# manpad.net
KiCad netlist of a schematic drawn in EAGLE
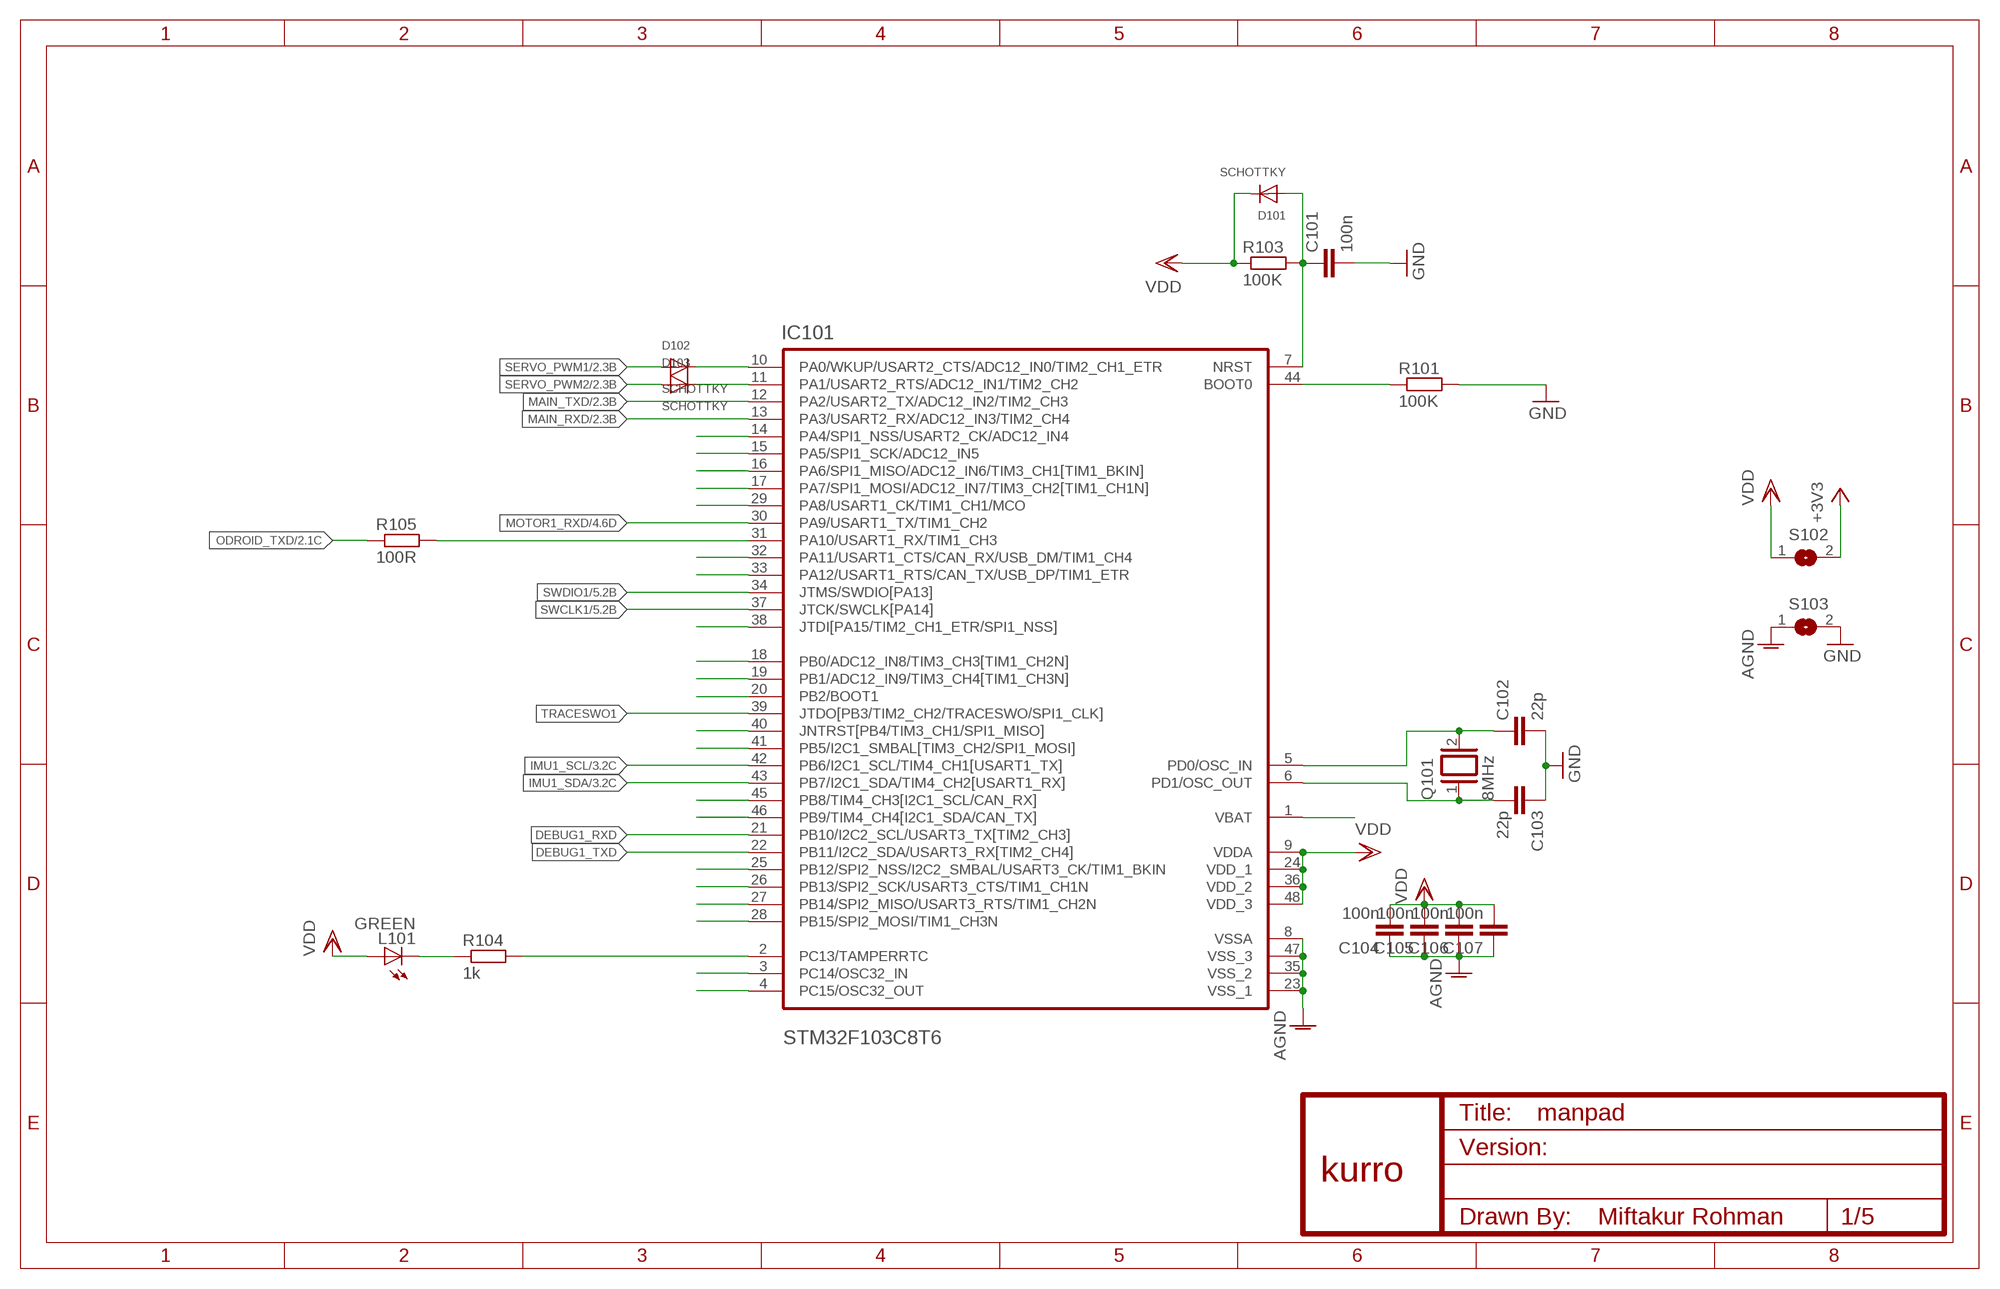
[diagram p0: schematic, sheet 1]
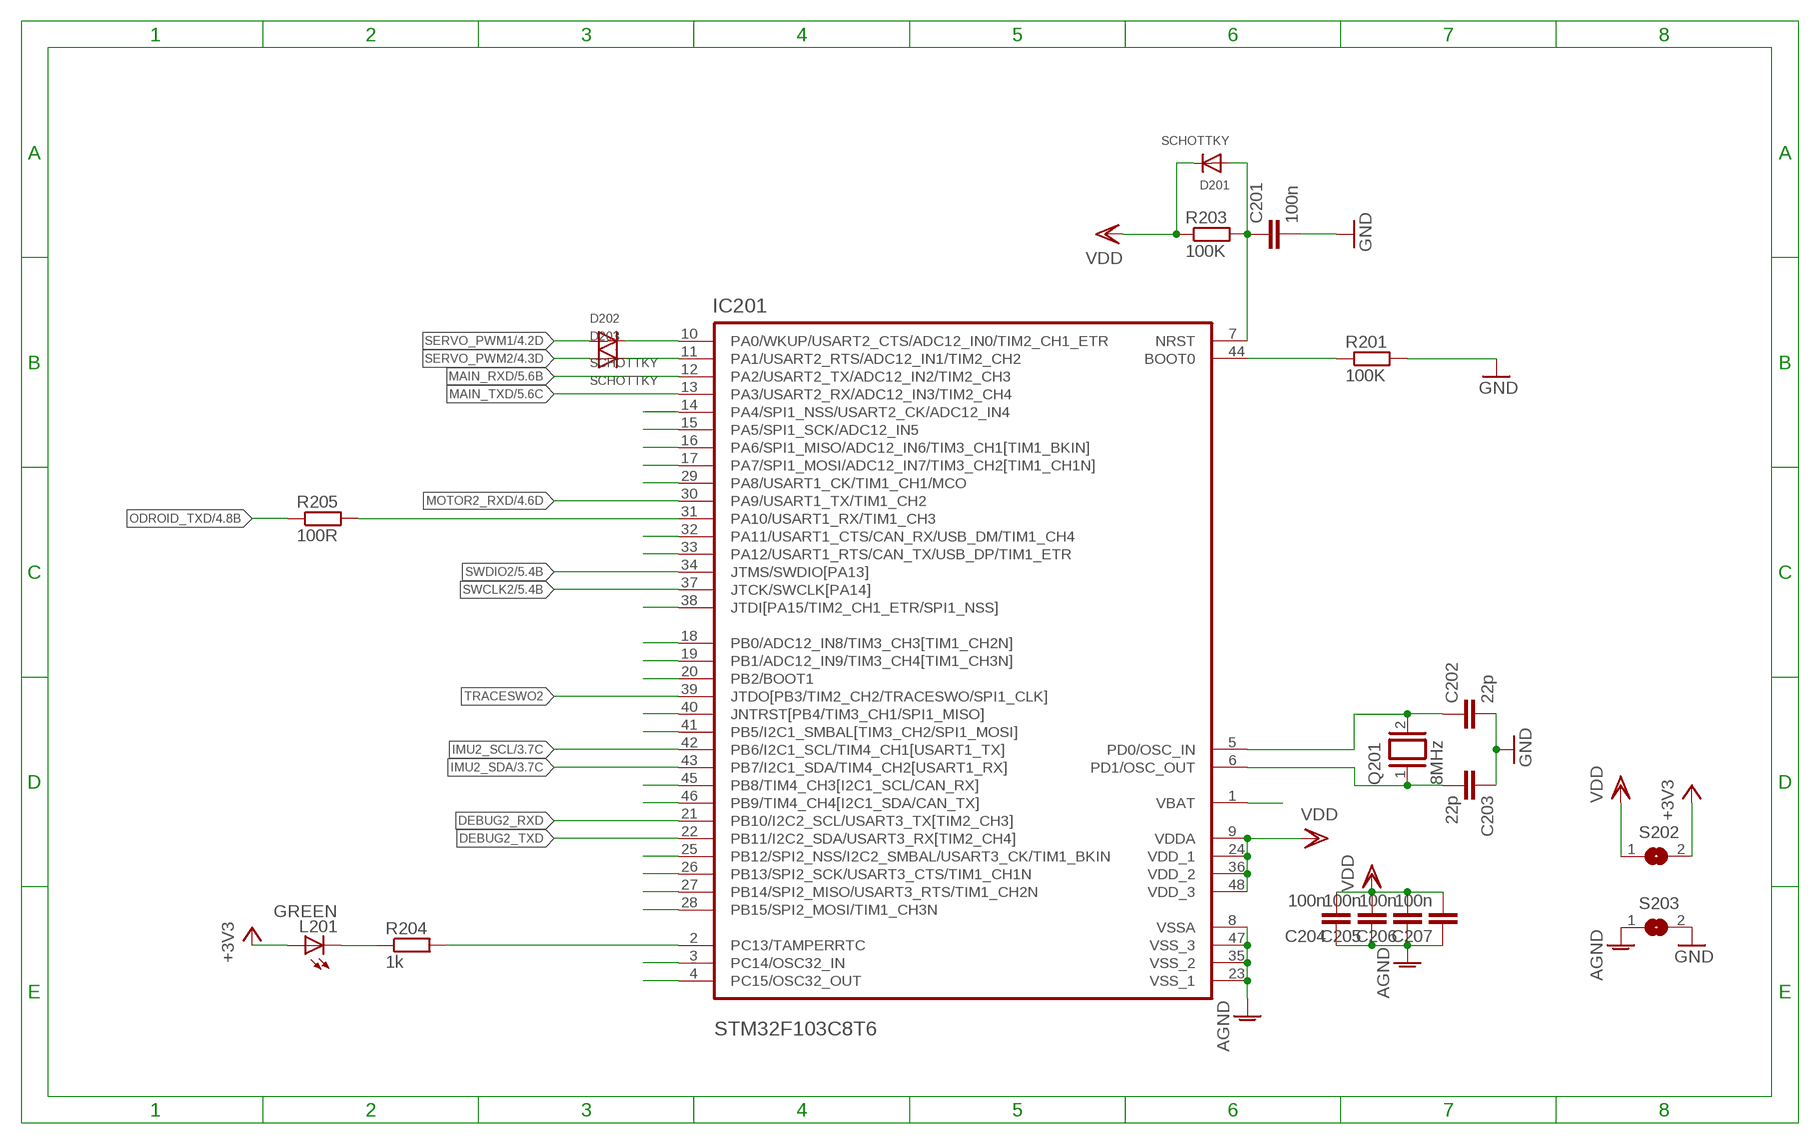
[diagram p1: schematic, sheet 2]
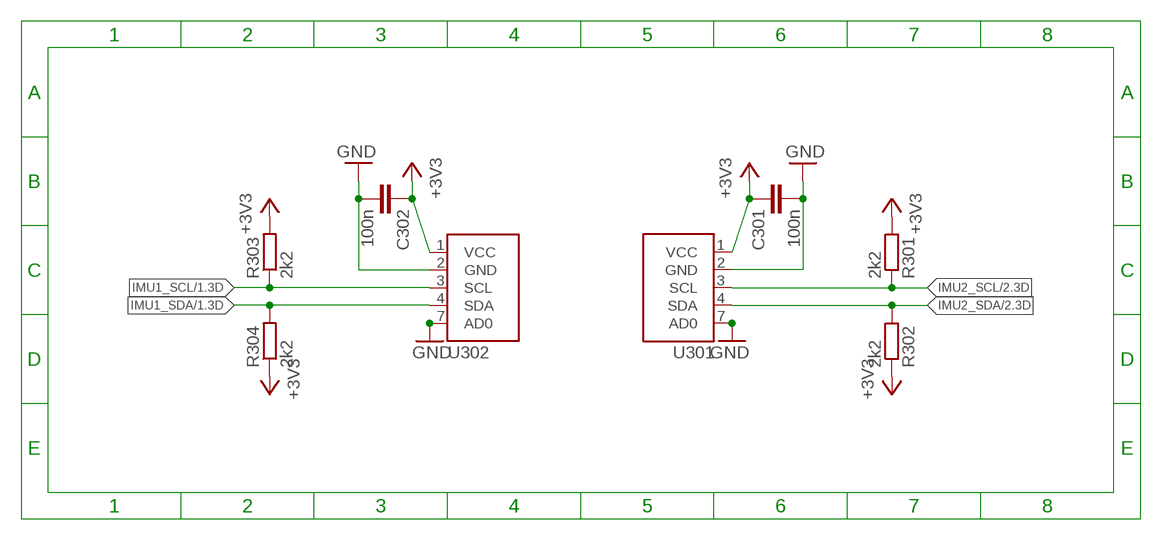
[diagram p2: schematic, sheet 3]
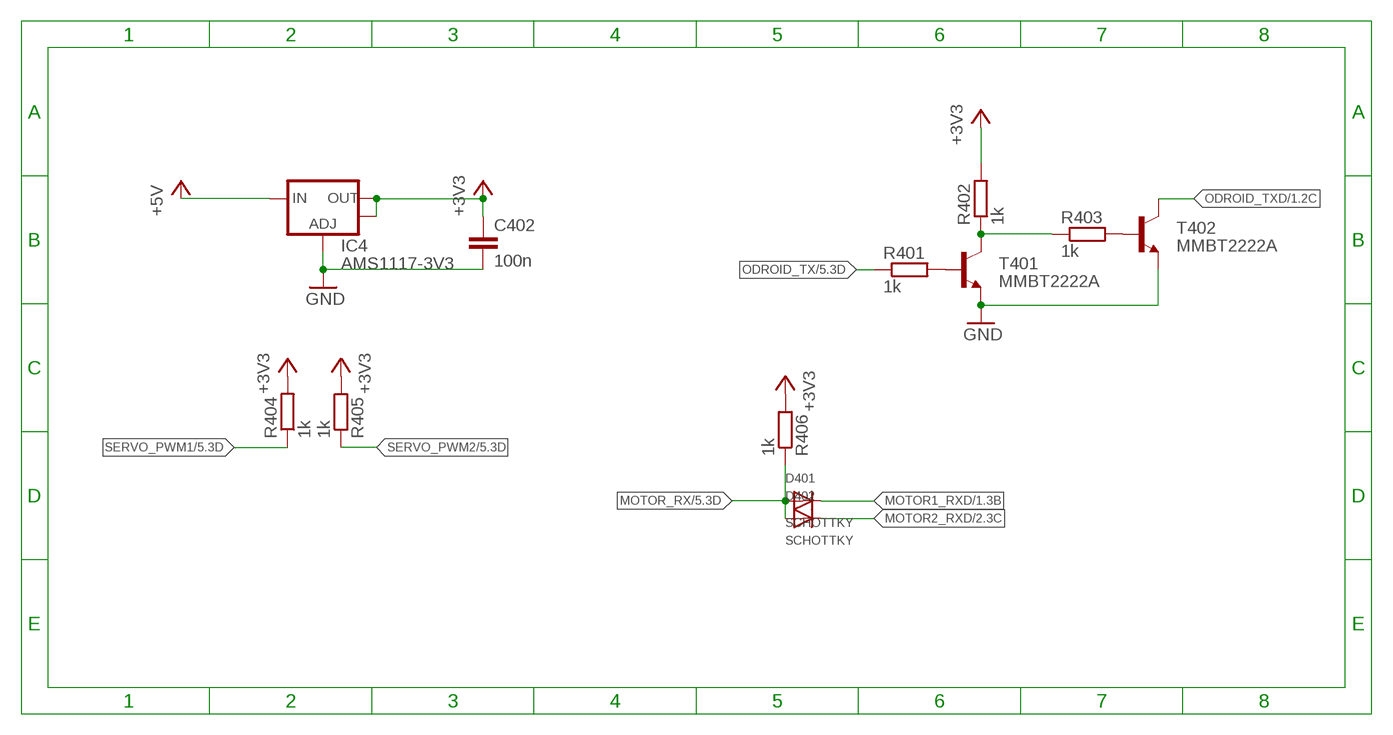
[diagram p3: schematic, sheet 4]
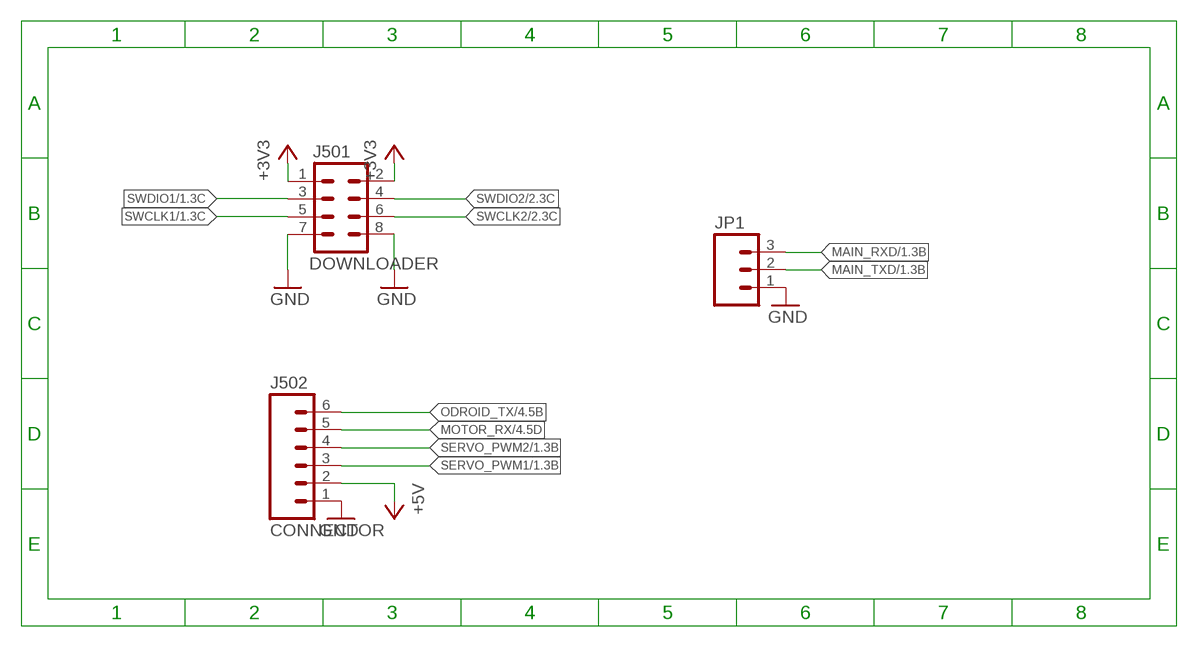
[diagram p4: schematic, sheet 5]

(export (version "E")
  (design (tool "Eeschema 10.0.6"))
  (components
    (comp (ref "C201")
      (value "100n")
      (footprint "eagle-import:C0603")
      (libsource (lib "eagle-import") (part "C-EUC0603"))
    )
    (comp (ref "C202")
      (value "22p")
      (footprint "eagle-import:C0603")
      (libsource (lib "eagle-import") (part "C-EUC0603"))
    )
    (comp (ref "C203")
      (value "22p")
      (footprint "eagle-import:C0603")
      (libsource (lib "eagle-import") (part "C-EUC0603"))
    )
    (comp (ref "C204")
      (value "100n")
      (footprint "eagle-import:C0603")
      (libsource (lib "eagle-import") (part "C-EUC0603"))
    )
    (comp (ref "C205")
      (value "100n")
      (footprint "eagle-import:C0603")
      (libsource (lib "eagle-import") (part "C-EUC0603"))
    )
    (comp (ref "C206")
      (value "100n")
      (footprint "eagle-import:C0603")
      (libsource (lib "eagle-import") (part "C-EUC0603"))
    )
    (comp (ref "C207")
      (value "100n")
      (footprint "eagle-import:C0603")
      (libsource (lib "eagle-import") (part "C-EUC0603"))
    )
    (comp (ref "D201")
      (value "SCHOTTKY")
      (footprint "eagle-import:SOD-323F")
      (libsource (lib "eagle-import") (part "DIODESOD-323F"))
    )
    (comp (ref "D202")
      (value "SCHOTTKY")
      (footprint "eagle-import:SOD-323F")
      (libsource (lib "eagle-import") (part "DIODESOD-323F"))
    )
    (comp (ref "D203")
      (value "SCHOTTKY")
      (footprint "eagle-import:SOD-323F")
      (libsource (lib "eagle-import") (part "DIODESOD-323F"))
    )
    (comp (ref "IC201")
      (value "STM32F103C8T6")
      (footprint "eagle-import:QFP50P900X900X160-48N")
      (fields (field (name "MPN") "STM32F103CBT6"))
      (libsource (lib "eagle-import") (part "STM32F103C8T6"))
    )
    (comp (ref "L201")
      (value "GREEN")
      (footprint "eagle-import:CHIP-LED0805")
      (libsource (lib "eagle-import") (part "LEDCHIP-LED0805"))
    )
    (comp (ref "Q201")
      (value "8MHz")
      (footprint "eagle-import:QS")
      (libsource (lib "eagle-import") (part "XTAL/S"))
    )
    (comp (ref "R201")
      (value "100K")
      (footprint "eagle-import:R0603")
      (libsource (lib "eagle-import") (part "R-EU_R0603"))
    )
    (comp (ref "R203")
      (value "100K")
      (footprint "eagle-import:R0603")
      (libsource (lib "eagle-import") (part "R-EU_R0603"))
    )
    (comp (ref "R204")
      (value "1k")
      (footprint "eagle-import:R0603")
      (libsource (lib "eagle-import") (part "R-EU_R0603"))
    )
    (comp (ref "R205")
      (value "100R")
      (footprint "eagle-import:R0603")
      (libsource (lib "eagle-import") (part "R-EU_R0603"))
    )
    (comp (ref "S202")
      (value "SJS")
      (footprint "eagle-import:SJS")
      (libsource (lib "eagle-import") (part "SJS"))
    )
    (comp (ref "S203")
      (value "SJS")
      (footprint "eagle-import:SJS")
      (libsource (lib "eagle-import") (part "SJS"))
    )
    (comp (ref "J501")
      (value "DOWNLOADER")
      (footprint "eagle-import:2X4_SMD")
      (libsource (lib "eagle-import") (part "M04X2FEMALE_SMD"))
    )
    (comp (ref "J502")
      (value "CONNECTOR")
      (footprint "eagle-import:XH-6-RA")
      (libsource (lib "eagle-import") (part "M06-XH-RA"))
    )
    (comp (ref "JP1")
      (value "M03LOCK")
      (footprint "eagle-import:1X03_LOCK")
      (libsource (lib "eagle-import") (part "M03LOCK"))
    )
    (comp (ref "C101")
      (value "100n")
      (footprint "eagle-import:C0603")
      (libsource (lib "eagle-import") (part "C-EUC0603"))
    )
    (comp (ref "C102")
      (value "22p")
      (footprint "eagle-import:C0603")
      (libsource (lib "eagle-import") (part "C-EUC0603"))
    )
    (comp (ref "C103")
      (value "22p")
      (footprint "eagle-import:C0603")
      (libsource (lib "eagle-import") (part "C-EUC0603"))
    )
    (comp (ref "C104")
      (value "100n")
      (footprint "eagle-import:C0603")
      (libsource (lib "eagle-import") (part "C-EUC0603"))
    )
    (comp (ref "C105")
      (value "100n")
      (footprint "eagle-import:C0603")
      (libsource (lib "eagle-import") (part "C-EUC0603"))
    )
    (comp (ref "C106")
      (value "100n")
      (footprint "eagle-import:C0603")
      (libsource (lib "eagle-import") (part "C-EUC0603"))
    )
    (comp (ref "C107")
      (value "100n")
      (footprint "eagle-import:C0603")
      (libsource (lib "eagle-import") (part "C-EUC0603"))
    )
    (comp (ref "D101")
      (value "SCHOTTKY")
      (footprint "eagle-import:SOD-323F")
      (libsource (lib "eagle-import") (part "DIODESOD-323F"))
    )
    (comp (ref "D102")
      (value "SCHOTTKY")
      (footprint "eagle-import:SOD-323F")
      (libsource (lib "eagle-import") (part "DIODESOD-323F"))
    )
    (comp (ref "D103")
      (value "SCHOTTKY")
      (footprint "eagle-import:SOD-323F")
      (libsource (lib "eagle-import") (part "DIODESOD-323F"))
    )
    (comp (ref "IC101")
      (value "STM32F103C8T6")
      (footprint "eagle-import:QFP50P900X900X160-48N")
      (fields (field (name "MPN") "STM32F103CBT6"))
      (libsource (lib "eagle-import") (part "STM32F103C8T6"))
    )
    (comp (ref "L101")
      (value "GREEN")
      (footprint "eagle-import:CHIP-LED0805")
      (libsource (lib "eagle-import") (part "LEDCHIP-LED0805"))
    )
    (comp (ref "Q101")
      (value "8MHz")
      (footprint "eagle-import:QS")
      (libsource (lib "eagle-import") (part "XTAL/S"))
    )
    (comp (ref "R101")
      (value "100K")
      (footprint "eagle-import:R0603")
      (libsource (lib "eagle-import") (part "R-EU_R0603"))
    )
    (comp (ref "R103")
      (value "100K")
      (footprint "eagle-import:R0603")
      (libsource (lib "eagle-import") (part "R-EU_R0603"))
    )
    (comp (ref "R104")
      (value "1k")
      (footprint "eagle-import:R0603")
      (libsource (lib "eagle-import") (part "R-EU_R0603"))
    )
    (comp (ref "R105")
      (value "100R")
      (footprint "eagle-import:R0603")
      (libsource (lib "eagle-import") (part "R-EU_R0603"))
    )
    (comp (ref "S102")
      (value "SJS")
      (footprint "eagle-import:SJS")
      (libsource (lib "eagle-import") (part "SJS"))
    )
    (comp (ref "S103")
      (value "SJS")
      (footprint "eagle-import:SJS")
      (libsource (lib "eagle-import") (part "SJS"))
    )
    (comp (ref "U$1")
      (value "KURRO_FOOTPRINT")
      (footprint "eagle-import:KURRO-LOGO")
      (libsource (lib "eagle-import") (part "KURRO_FOOTPRINT"))
    )
    (comp (ref "C402")
      (value "100n")
      (footprint "eagle-import:C0603")
      (libsource (lib "eagle-import") (part "C-EUC0603"))
    )
    (comp (ref "D401")
      (value "SCHOTTKY")
      (footprint "eagle-import:SOD-323F")
      (libsource (lib "eagle-import") (part "DIODESOD-323F"))
    )
    (comp (ref "D402")
      (value "SCHOTTKY")
      (footprint "eagle-import:SOD-323F")
      (libsource (lib "eagle-import") (part "DIODESOD-323F"))
    )
    (comp (ref "IC4")
      (value "AMS1117-3V3")
      (footprint "eagle-import:SOT223")
      (libsource (lib "eagle-import") (part "V_REG_LM1117SOT223"))
    )
    (comp (ref "R401")
      (value "1k")
      (footprint "eagle-import:R0603")
      (libsource (lib "eagle-import") (part "R-EU_R0603"))
    )
    (comp (ref "R402")
      (value "1k")
      (footprint "eagle-import:R0603")
      (libsource (lib "eagle-import") (part "R-EU_R0603"))
    )
    (comp (ref "R403")
      (value "1k")
      (footprint "eagle-import:R0603")
      (libsource (lib "eagle-import") (part "R-EU_R0603"))
    )
    (comp (ref "R404")
      (value "1k")
      (footprint "eagle-import:R0603")
      (libsource (lib "eagle-import") (part "R-EU_R0603"))
    )
    (comp (ref "R405")
      (value "1k")
      (footprint "eagle-import:R0603")
      (libsource (lib "eagle-import") (part "R-EU_R0603"))
    )
    (comp (ref "R406")
      (value "1k")
      (footprint "eagle-import:R0603")
      (libsource (lib "eagle-import") (part "R-EU_R0603"))
    )
    (comp (ref "T401")
      (value "MMBT2222A")
      (footprint "eagle-import:SOT23")
      (libsource (lib "eagle-import") (part "TRANSISTOR_NPNSOT23"))
    )
    (comp (ref "T402")
      (value "MMBT2222A")
      (footprint "eagle-import:SOT23")
      (libsource (lib "eagle-import") (part "TRANSISTOR_NPNSOT23"))
    )
    (comp (ref "C301")
      (value "100n")
      (footprint "eagle-import:C0603")
      (libsource (lib "eagle-import") (part "C-EUC0603"))
    )
    (comp (ref "C302")
      (value "100n")
      (footprint "eagle-import:C0603")
      (libsource (lib "eagle-import") (part "C-EUC0603"))
    )
    (comp (ref "R301")
      (value "2k2")
      (footprint "eagle-import:R0603")
      (libsource (lib "eagle-import") (part "R-EU_R0603"))
    )
    (comp (ref "R302")
      (value "2k2")
      (footprint "eagle-import:R0603")
      (libsource (lib "eagle-import") (part "R-EU_R0603"))
    )
    (comp (ref "R303")
      (value "2k2")
      (footprint "eagle-import:R0603")
      (libsource (lib "eagle-import") (part "R-EU_R0603"))
    )
    (comp (ref "R304")
      (value "2k2")
      (footprint "eagle-import:R0603")
      (libsource (lib "eagle-import") (part "R-EU_R0603"))
    )
    (comp (ref "U301")
      (value "GY-521_MIN")
      (footprint "eagle-import:GY-521_MINNH")
      (libsource (lib "eagle-import") (part "GY-521_MIN"))
    )
    (comp (ref "U302")
      (value "GY-521_MIN")
      (footprint "eagle-import:GY-521_MINNH")
      (libsource (lib "eagle-import") (part "GY-521_MIN"))
    )
  )
  (nets
    (net (code "1") (name "+3V3") (class "Default")
      (node (ref "C301") (pin "1") (pinfunction "1_1") (pintype "passive"))
      (node (ref "C302") (pin "1") (pinfunction "1_1") (pintype "passive"))
      (node (ref "C402") (pin "1") (pinfunction "1_1") (pintype "passive"))
      (node (ref "IC4") (pin "2") (pinfunction "OUT_2") (pintype "power_in"))
      (node (ref "IC4") (pin "4") (pinfunction "OUT_4") (pintype "power_in"))
      (node (ref "J501") (pin "1") (pinfunction "1_1") (pintype "passive"))
      (node (ref "J501") (pin "2") (pinfunction "2_2") (pintype "passive"))
      (node (ref "L201") (pin "A") (pinfunction "A_A") (pintype "passive"))
      (node (ref "R301") (pin "2") (pinfunction "2_2") (pintype "passive"))
      (node (ref "R302") (pin "1") (pinfunction "1_1") (pintype "passive"))
      (node (ref "R303") (pin "2") (pinfunction "2_2") (pintype "passive"))
      (node (ref "R304") (pin "1") (pinfunction "1_1") (pintype "passive"))
      (node (ref "R402") (pin "2") (pinfunction "2_2") (pintype "passive"))
      (node (ref "R404") (pin "2") (pinfunction "2_2") (pintype "passive"))
      (node (ref "R405") (pin "2") (pinfunction "2_2") (pintype "passive"))
      (node (ref "R406") (pin "2") (pinfunction "2_2") (pintype "passive"))
      (node (ref "S102") (pin "2") (pinfunction "2_2") (pintype "passive"))
      (node (ref "S202") (pin "2") (pinfunction "2_2") (pintype "passive"))
      (node (ref "U301") (pin "1") (pinfunction "VCC_1") (pintype "bidirectional"))
      (node (ref "U302") (pin "1") (pinfunction "VCC_1") (pintype "bidirectional"))
    )
    (net (code "2") (name "+5V") (class "Default")
      (node (ref "IC4") (pin "3") (pinfunction "IN_3") (pintype "input"))
      (node (ref "J502") (pin "2") (pinfunction "2_2") (pintype "passive"))
    )
    (net (code "3") (name "AGND") (class "Default")
      (node (ref "C104") (pin "1") (pinfunction "1_1") (pintype "passive"))
      (node (ref "C105") (pin "1") (pinfunction "1_1") (pintype "passive"))
      (node (ref "C106") (pin "1") (pinfunction "1_1") (pintype "passive"))
      (node (ref "C107") (pin "1") (pinfunction "1_1") (pintype "passive"))
      (node (ref "C204") (pin "1") (pinfunction "1_1") (pintype "passive"))
      (node (ref "C205") (pin "1") (pinfunction "1_1") (pintype "passive"))
      (node (ref "C206") (pin "1") (pinfunction "1_1") (pintype "passive"))
      (node (ref "C207") (pin "1") (pinfunction "1_1") (pintype "passive"))
      (node (ref "IC101") (pin "23") (pinfunction "VSS_1_23") (pintype "bidirectional"))
      (node (ref "IC101") (pin "35") (pinfunction "VSS_2_35") (pintype "passive"))
      (node (ref "IC101") (pin "47") (pinfunction "VSS_3_47") (pintype "passive"))
      (node (ref "IC101") (pin "8") (pinfunction "VSSA_8") (pintype "passive"))
      (node (ref "IC201") (pin "23") (pinfunction "VSS_1_23") (pintype "bidirectional"))
      (node (ref "IC201") (pin "35") (pinfunction "VSS_2_35") (pintype "passive"))
      (node (ref "IC201") (pin "47") (pinfunction "VSS_3_47") (pintype "passive"))
      (node (ref "IC201") (pin "8") (pinfunction "VSSA_8") (pintype "passive"))
      (node (ref "S103") (pin "1") (pinfunction "1_1") (pintype "passive"))
      (node (ref "S203") (pin "1") (pinfunction "1_1") (pintype "passive"))
    )
    (net (code "4") (name "DEBUG1_RXD") (class "Default")
      (node (ref "IC101") (pin "21") (pinfunction "PB10/I2C2_SCL/USART3_TX[TIM2_CH3]_21") (pintype "bidirectional"))
    )
    (net (code "5") (name "DEBUG1_TXD") (class "Default")
      (node (ref "IC101") (pin "22") (pinfunction "PB11/I2C2_SDA/USART3_RX[TIM2_CH4]_22") (pintype "bidirectional"))
    )
    (net (code "6") (name "DEBUG2_RXD") (class "Default")
      (node (ref "IC201") (pin "21") (pinfunction "PB10/I2C2_SCL/USART3_TX[TIM2_CH3]_21") (pintype "bidirectional"))
    )
    (net (code "7") (name "DEBUG2_TXD") (class "Default")
      (node (ref "IC201") (pin "22") (pinfunction "PB11/I2C2_SDA/USART3_RX[TIM2_CH4]_22") (pintype "bidirectional"))
    )
    (net (code "8") (name "GND") (class "Default")
      (node (ref "C101") (pin "2") (pinfunction "2_2") (pintype "passive"))
      (node (ref "C102") (pin "2") (pinfunction "2_2") (pintype "passive"))
      (node (ref "C103") (pin "1") (pinfunction "1_1") (pintype "passive"))
      (node (ref "C201") (pin "2") (pinfunction "2_2") (pintype "passive"))
      (node (ref "C202") (pin "2") (pinfunction "2_2") (pintype "passive"))
      (node (ref "C203") (pin "1") (pinfunction "1_1") (pintype "passive"))
      (node (ref "C301") (pin "2") (pinfunction "2_2") (pintype "passive"))
      (node (ref "C302") (pin "2") (pinfunction "2_2") (pintype "passive"))
      (node (ref "C402") (pin "2") (pinfunction "2_2") (pintype "passive"))
      (node (ref "IC4") (pin "1") (pinfunction "ADJ_1") (pintype "input"))
      (node (ref "J501") (pin "7") (pinfunction "7_7") (pintype "passive"))
      (node (ref "J501") (pin "8") (pinfunction "8_8") (pintype "passive"))
      (node (ref "J502") (pin "1") (pinfunction "1_1") (pintype "passive"))
      (node (ref "JP1") (pin "1") (pinfunction "1_1") (pintype "passive"))
      (node (ref "R101") (pin "2") (pinfunction "2_2") (pintype "passive"))
      (node (ref "R201") (pin "2") (pinfunction "2_2") (pintype "passive"))
      (node (ref "S103") (pin "2") (pinfunction "2_2") (pintype "passive"))
      (node (ref "S203") (pin "2") (pinfunction "2_2") (pintype "passive"))
      (node (ref "T401") (pin "2") (pinfunction "E_2") (pintype "passive"))
      (node (ref "T402") (pin "2") (pinfunction "E_2") (pintype "passive"))
      (node (ref "U301") (pin "2") (pinfunction "GND_2") (pintype "bidirectional"))
      (node (ref "U301") (pin "7") (pinfunction "AD0_7") (pintype "bidirectional"))
      (node (ref "U302") (pin "2") (pinfunction "GND_2") (pintype "bidirectional"))
      (node (ref "U302") (pin "7") (pinfunction "AD0_7") (pintype "bidirectional"))
    )
    (net (code "9") (name "IMU1_SCL") (class "Default")
      (node (ref "IC101") (pin "42") (pinfunction "PB6/I2C1_SCL/TIM4_CH1[USART1_TX]_42") (pintype "bidirectional"))
      (node (ref "R303") (pin "1") (pinfunction "1_1") (pintype "passive"))
      (node (ref "U302") (pin "3") (pinfunction "SCL_3") (pintype "bidirectional"))
    )
    (net (code "10") (name "IMU1_SDA") (class "Default")
      (node (ref "IC101") (pin "43") (pinfunction "PB7/I2C1_SDA/TIM4_CH2[USART1_RX]_43") (pintype "bidirectional"))
      (node (ref "R304") (pin "2") (pinfunction "2_2") (pintype "passive"))
      (node (ref "U302") (pin "4") (pinfunction "SDA_4") (pintype "bidirectional"))
    )
    (net (code "11") (name "IMU2_SCL") (class "Default")
      (node (ref "IC201") (pin "42") (pinfunction "PB6/I2C1_SCL/TIM4_CH1[USART1_TX]_42") (pintype "bidirectional"))
      (node (ref "R301") (pin "1") (pinfunction "1_1") (pintype "passive"))
      (node (ref "U301") (pin "3") (pinfunction "SCL_3") (pintype "bidirectional"))
    )
    (net (code "12") (name "IMU2_SDA") (class "Default")
      (node (ref "IC201") (pin "43") (pinfunction "PB7/I2C1_SDA/TIM4_CH2[USART1_RX]_43") (pintype "bidirectional"))
      (node (ref "R302") (pin "2") (pinfunction "2_2") (pintype "passive"))
      (node (ref "U301") (pin "4") (pinfunction "SDA_4") (pintype "bidirectional"))
    )
    (net (code "13") (name "MAIN_RXD") (class "Default")
      (node (ref "IC101") (pin "13") (pinfunction "PA3/USART2_RX/ADC12_IN3/TIM2_CH4_13") (pintype "bidirectional"))
      (node (ref "IC201") (pin "12") (pinfunction "PA2/USART2_TX/ADC12_IN2/TIM2_CH3_12") (pintype "bidirectional"))
      (node (ref "JP1") (pin "3") (pinfunction "3_3") (pintype "passive"))
    )
    (net (code "14") (name "MAIN_TXD") (class "Default")
      (node (ref "IC101") (pin "12") (pinfunction "PA2/USART2_TX/ADC12_IN2/TIM2_CH3_12") (pintype "bidirectional"))
      (node (ref "IC201") (pin "13") (pinfunction "PA3/USART2_RX/ADC12_IN3/TIM2_CH4_13") (pintype "bidirectional"))
      (node (ref "JP1") (pin "2") (pinfunction "2_2") (pintype "passive"))
    )
    (net (code "15") (name "MOTOR1_RXD") (class "Default")
      (node (ref "D401") (pin "C") (pinfunction "C_C") (pintype "passive"))
      (node (ref "IC101") (pin "30") (pinfunction "PA9/USART1_TX/TIM1_CH2_30") (pintype "bidirectional"))
    )
    (net (code "16") (name "MOTOR2_RXD") (class "Default")
      (node (ref "D402") (pin "C") (pinfunction "C_C") (pintype "passive"))
      (node (ref "IC201") (pin "30") (pinfunction "PA9/USART1_TX/TIM1_CH2_30") (pintype "bidirectional"))
    )
    (net (code "17") (name "MOTOR_RX") (class "Default")
      (node (ref "D401") (pin "A") (pinfunction "A_A") (pintype "passive"))
      (node (ref "D402") (pin "A") (pinfunction "A_A") (pintype "passive"))
      (node (ref "J502") (pin "5") (pinfunction "5_5") (pintype "passive"))
      (node (ref "R406") (pin "1") (pinfunction "1_1") (pintype "passive"))
    )
    (net (code "18") (name "Net-(IC101-BOOT0)") (class "Default")
      (node (ref "IC101") (pin "44") (pinfunction "BOOT0_44") (pintype "bidirectional"))
      (node (ref "R101") (pin "1") (pinfunction "1_1") (pintype "passive"))
    )
    (net (code "19") (name "Net-(IC101-NRST)") (class "Default")
      (node (ref "C101") (pin "1") (pinfunction "1_1") (pintype "passive"))
      (node (ref "D101") (pin "A") (pinfunction "A_A") (pintype "passive"))
      (node (ref "IC101") (pin "7") (pinfunction "NRST_7") (pintype "bidirectional"))
      (node (ref "R103") (pin "2") (pinfunction "2_2") (pintype "passive"))
    )
    (net (code "20") (name "Net-(IC101-PA0{slash}WKUP{slash}USART2_CTS{slash}ADC12_IN0{slash}TIM2_CH1_ETR)") (class "Default")
      (node (ref "D102") (pin "C") (pinfunction "C_C") (pintype "passive"))
      (node (ref "IC101") (pin "10") (pinfunction "PA0/WKUP/USART2_CTS/ADC12_IN0/TIM2_CH1_ETR_10") (pintype "bidirectional"))
    )
    (net (code "21") (name "Net-(IC101-PA1{slash}USART2_RTS{slash}ADC12_IN1{slash}TIM2_CH2)") (class "Default")
      (node (ref "D103") (pin "C") (pinfunction "C_C") (pintype "passive"))
      (node (ref "IC101") (pin "11") (pinfunction "PA1/USART2_RTS/ADC12_IN1/TIM2_CH2_11") (pintype "bidirectional"))
    )
    (net (code "22") (name "Net-(IC101-PA10{slash}USART1_RX{slash}TIM1_CH3)") (class "Default")
      (node (ref "IC101") (pin "31") (pinfunction "PA10/USART1_RX/TIM1_CH3_31") (pintype "bidirectional"))
      (node (ref "R105") (pin "2") (pinfunction "2_2") (pintype "passive"))
    )
    (net (code "23") (name "Net-(IC101-PC13{slash}TAMPERRTC)") (class "Default")
      (node (ref "IC101") (pin "2") (pinfunction "PC13/TAMPERRTC_2") (pintype "bidirectional"))
      (node (ref "R104") (pin "2") (pinfunction "2_2") (pintype "passive"))
    )
    (net (code "24") (name "Net-(IC101-PD0{slash}OSC_IN)") (class "Default")
      (node (ref "C102") (pin "1") (pinfunction "1_1") (pintype "passive"))
      (node (ref "IC101") (pin "5") (pinfunction "PD0/OSC_IN_5") (pintype "bidirectional"))
      (node (ref "Q101") (pin "2") (pinfunction "2_2") (pintype "passive"))
    )
    (net (code "25") (name "Net-(IC101-PD1{slash}OSC_OUT)") (class "Default")
      (node (ref "C103") (pin "2") (pinfunction "2_2") (pintype "passive"))
      (node (ref "IC101") (pin "6") (pinfunction "PD1/OSC_OUT_6") (pintype "bidirectional"))
      (node (ref "Q101") (pin "1") (pinfunction "1_1") (pintype "passive"))
    )
    (net (code "26") (name "Net-(IC201-BOOT0)") (class "Default")
      (node (ref "IC201") (pin "44") (pinfunction "BOOT0_44") (pintype "bidirectional"))
      (node (ref "R201") (pin "1") (pinfunction "1_1") (pintype "passive"))
    )
    (net (code "27") (name "Net-(IC201-NRST)") (class "Default")
      (node (ref "C201") (pin "1") (pinfunction "1_1") (pintype "passive"))
      (node (ref "D201") (pin "A") (pinfunction "A_A") (pintype "passive"))
      (node (ref "IC201") (pin "7") (pinfunction "NRST_7") (pintype "bidirectional"))
      (node (ref "R203") (pin "2") (pinfunction "2_2") (pintype "passive"))
    )
    (net (code "28") (name "Net-(IC201-PA0{slash}WKUP{slash}USART2_CTS{slash}ADC12_IN0{slash}TIM2_CH1_ETR)") (class "Default")
      (node (ref "D202") (pin "C") (pinfunction "C_C") (pintype "passive"))
      (node (ref "IC201") (pin "10") (pinfunction "PA0/WKUP/USART2_CTS/ADC12_IN0/TIM2_CH1_ETR_10") (pintype "bidirectional"))
    )
    (net (code "29") (name "Net-(IC201-PA1{slash}USART2_RTS{slash}ADC12_IN1{slash}TIM2_CH2)") (class "Default")
      (node (ref "D203") (pin "C") (pinfunction "C_C") (pintype "passive"))
      (node (ref "IC201") (pin "11") (pinfunction "PA1/USART2_RTS/ADC12_IN1/TIM2_CH2_11") (pintype "bidirectional"))
    )
    (net (code "30") (name "Net-(IC201-PA10{slash}USART1_RX{slash}TIM1_CH3)") (class "Default")
      (node (ref "IC201") (pin "31") (pinfunction "PA10/USART1_RX/TIM1_CH3_31") (pintype "bidirectional"))
      (node (ref "R205") (pin "2") (pinfunction "2_2") (pintype "passive"))
    )
    (net (code "31") (name "Net-(IC201-PC13{slash}TAMPERRTC)") (class "Default")
      (node (ref "IC201") (pin "2") (pinfunction "PC13/TAMPERRTC_2") (pintype "bidirectional"))
      (node (ref "R204") (pin "2") (pinfunction "2_2") (pintype "passive"))
    )
    (net (code "32") (name "Net-(IC201-PD0{slash}OSC_IN)") (class "Default")
      (node (ref "C202") (pin "1") (pinfunction "1_1") (pintype "passive"))
      (node (ref "IC201") (pin "5") (pinfunction "PD0/OSC_IN_5") (pintype "bidirectional"))
      (node (ref "Q201") (pin "2") (pinfunction "2_2") (pintype "passive"))
    )
    (net (code "33") (name "Net-(IC201-PD1{slash}OSC_OUT)") (class "Default")
      (node (ref "C203") (pin "2") (pinfunction "2_2") (pintype "passive"))
      (node (ref "IC201") (pin "6") (pinfunction "PD1/OSC_OUT_6") (pintype "bidirectional"))
      (node (ref "Q201") (pin "1") (pinfunction "1_1") (pintype "passive"))
    )
    (net (code "34") (name "Net-(L101-PadC)") (class "Default")
      (node (ref "L101") (pin "C") (pinfunction "C_C") (pintype "passive"))
      (node (ref "R104") (pin "1") (pinfunction "1_1") (pintype "passive"))
    )
    (net (code "35") (name "Net-(L201-PadC)") (class "Default")
      (node (ref "L201") (pin "C") (pinfunction "C_C") (pintype "passive"))
      (node (ref "R204") (pin "1") (pinfunction "1_1") (pintype "passive"))
    )
    (net (code "36") (name "Net-(T401-B)") (class "Default")
      (node (ref "R401") (pin "2") (pinfunction "2_2") (pintype "passive"))
      (node (ref "T401") (pin "1") (pinfunction "B_1") (pintype "passive"))
    )
    (net (code "37") (name "Net-(T401-C)") (class "Default")
      (node (ref "R402") (pin "1") (pinfunction "1_1") (pintype "passive"))
      (node (ref "R403") (pin "1") (pinfunction "1_1") (pintype "passive"))
      (node (ref "T401") (pin "3") (pinfunction "C_3") (pintype "passive"))
    )
    (net (code "38") (name "Net-(T402-B)") (class "Default")
      (node (ref "R403") (pin "2") (pinfunction "2_2") (pintype "passive"))
      (node (ref "T402") (pin "1") (pinfunction "B_1") (pintype "passive"))
    )
    (net (code "39") (name "ODROID_TX") (class "Default")
      (node (ref "J502") (pin "6") (pinfunction "6_6") (pintype "passive"))
      (node (ref "R401") (pin "1") (pinfunction "1_1") (pintype "passive"))
    )
    (net (code "40") (name "ODROID_TXD") (class "Default")
      (node (ref "R105") (pin "1") (pinfunction "1_1") (pintype "passive"))
      (node (ref "R205") (pin "1") (pinfunction "1_1") (pintype "passive"))
      (node (ref "T402") (pin "3") (pinfunction "C_3") (pintype "passive"))
    )
    (net (code "41") (name "SERVO_PWM1") (class "Default")
      (node (ref "D102") (pin "A") (pinfunction "A_A") (pintype "passive"))
      (node (ref "D202") (pin "A") (pinfunction "A_A") (pintype "passive"))
      (node (ref "J502") (pin "3") (pinfunction "3_3") (pintype "passive"))
      (node (ref "R404") (pin "1") (pinfunction "1_1") (pintype "passive"))
    )
    (net (code "42") (name "SERVO_PWM2") (class "Default")
      (node (ref "D103") (pin "A") (pinfunction "A_A") (pintype "passive"))
      (node (ref "D203") (pin "A") (pinfunction "A_A") (pintype "passive"))
      (node (ref "J502") (pin "4") (pinfunction "4_4") (pintype "passive"))
      (node (ref "R405") (pin "1") (pinfunction "1_1") (pintype "passive"))
    )
    (net (code "43") (name "SWCLK1") (class "Default")
      (node (ref "IC101") (pin "37") (pinfunction "JTCK/SWCLK[PA14]_37") (pintype "bidirectional"))
      (node (ref "J501") (pin "5") (pinfunction "5_5") (pintype "passive"))
    )
    (net (code "44") (name "SWCLK2") (class "Default")
      (node (ref "IC201") (pin "37") (pinfunction "JTCK/SWCLK[PA14]_37") (pintype "bidirectional"))
      (node (ref "J501") (pin "6") (pinfunction "6_6") (pintype "passive"))
    )
    (net (code "45") (name "SWDIO1") (class "Default")
      (node (ref "IC101") (pin "34") (pinfunction "JTMS/SWDIO[PA13]_34") (pintype "bidirectional"))
      (node (ref "J501") (pin "3") (pinfunction "3_3") (pintype "passive"))
    )
    (net (code "46") (name "SWDIO2") (class "Default")
      (node (ref "IC201") (pin "34") (pinfunction "JTMS/SWDIO[PA13]_34") (pintype "bidirectional"))
      (node (ref "J501") (pin "4") (pinfunction "4_4") (pintype "passive"))
    )
    (net (code "47") (name "TRACESWO1") (class "Default")
      (node (ref "IC101") (pin "39") (pinfunction "JTDO[PB3/TIM2_CH2/TRACESWO/SPI1_CLK]_39") (pintype "bidirectional"))
    )
    (net (code "48") (name "TRACESWO2") (class "Default")
      (node (ref "IC201") (pin "39") (pinfunction "JTDO[PB3/TIM2_CH2/TRACESWO/SPI1_CLK]_39") (pintype "bidirectional"))
    )
    (net (code "49") (name "VDD") (class "Default")
      (node (ref "C104") (pin "2") (pinfunction "2_2") (pintype "passive"))
      (node (ref "C105") (pin "2") (pinfunction "2_2") (pintype "passive"))
      (node (ref "C106") (pin "2") (pinfunction "2_2") (pintype "passive"))
      (node (ref "C107") (pin "2") (pinfunction "2_2") (pintype "passive"))
      (node (ref "C204") (pin "2") (pinfunction "2_2") (pintype "passive"))
      (node (ref "C205") (pin "2") (pinfunction "2_2") (pintype "passive"))
      (node (ref "C206") (pin "2") (pinfunction "2_2") (pintype "passive"))
      (node (ref "C207") (pin "2") (pinfunction "2_2") (pintype "passive"))
      (node (ref "D101") (pin "C") (pinfunction "C_C") (pintype "passive"))
      (node (ref "D201") (pin "C") (pinfunction "C_C") (pintype "passive"))
      (node (ref "IC101") (pin "24") (pinfunction "VDD_1_24") (pintype "bidirectional"))
      (node (ref "IC101") (pin "36") (pinfunction "VDD_2_36") (pintype "power_in"))
      (node (ref "IC101") (pin "48") (pinfunction "VDD_3_48") (pintype "power_in"))
      (node (ref "IC101") (pin "9") (pinfunction "VDDA_9") (pintype "power_in"))
      (node (ref "IC201") (pin "24") (pinfunction "VDD_1_24") (pintype "bidirectional"))
      (node (ref "IC201") (pin "36") (pinfunction "VDD_2_36") (pintype "power_in"))
      (node (ref "IC201") (pin "48") (pinfunction "VDD_3_48") (pintype "power_in"))
      (node (ref "IC201") (pin "9") (pinfunction "VDDA_9") (pintype "power_in"))
      (node (ref "L101") (pin "A") (pinfunction "A_A") (pintype "passive"))
      (node (ref "R103") (pin "1") (pinfunction "1_1") (pintype "passive"))
      (node (ref "R203") (pin "1") (pinfunction "1_1") (pintype "passive"))
      (node (ref "S102") (pin "1") (pinfunction "1_1") (pintype "passive"))
      (node (ref "S202") (pin "1") (pinfunction "1_1") (pintype "passive"))
    )
    (net (code "50") (name "unconnected-(IC101-JNTRST[PB4{slash}TIM3_CH1{slash}SPI1_MISO]-Pad40)") (class "Default")
      (node (ref "IC101") (pin "40") (pinfunction "JNTRST[PB4/TIM3_CH1/SPI1_MISO]_40") (pintype "bidirectional"))
    )
    (net (code "51") (name "unconnected-(IC101-JTDI[PA15{slash}TIM2_CH1_ETR{slash}SPI1_NSS]-Pad38)") (class "Default")
      (node (ref "IC101") (pin "38") (pinfunction "JTDI[PA15/TIM2_CH1_ETR/SPI1_NSS]_38") (pintype "bidirectional"))
    )
    (net (code "52") (name "unconnected-(IC101-PA4{slash}SPI1_NSS{slash}USART2_CK{slash}ADC12_IN4-Pad14)") (class "Default")
      (node (ref "IC101") (pin "14") (pinfunction "PA4/SPI1_NSS/USART2_CK/ADC12_IN4_14") (pintype "bidirectional"))
    )
    (net (code "53") (name "unconnected-(IC101-PA5{slash}SPI1_SCK{slash}ADC12_IN5-Pad15)") (class "Default")
      (node (ref "IC101") (pin "15") (pinfunction "PA5/SPI1_SCK/ADC12_IN5_15") (pintype "bidirectional"))
    )
    (net (code "54") (name "unconnected-(IC101-PA6{slash}SPI1_MISO{slash}ADC12_IN6{slash}TIM3_CH1[TIM1_BKIN]-Pad16)") (class "Default")
      (node (ref "IC101") (pin "16") (pinfunction "PA6/SPI1_MISO/ADC12_IN6/TIM3_CH1[TIM1_BKIN]_16") (pintype "bidirectional"))
    )
    (net (code "55") (name "unconnected-(IC101-PA7{slash}SPI1_MOSI{slash}ADC12_IN7{slash}TIM3_CH2[TIM1_CH1N]-Pad17)") (class "Default")
      (node (ref "IC101") (pin "17") (pinfunction "PA7/SPI1_MOSI/ADC12_IN7/TIM3_CH2[TIM1_CH1N]_17") (pintype "bidirectional"))
    )
    (net (code "56") (name "unconnected-(IC101-PA8{slash}USART1_CK{slash}TIM1_CH1{slash}MCO-Pad29)") (class "Default")
      (node (ref "IC101") (pin "29") (pinfunction "PA8/USART1_CK/TIM1_CH1/MCO_29") (pintype "bidirectional"))
    )
    (net (code "57") (name "unconnected-(IC101-PA11{slash}USART1_CTS{slash}CAN_RX{slash}USB_DM{slash}TIM1_CH4-Pad32)") (class "Default")
      (node (ref "IC101") (pin "32") (pinfunction "PA11/USART1_CTS/CAN_RX/USB_DM/TIM1_CH4_32") (pintype "power_in"))
    )
    (net (code "58") (name "unconnected-(IC101-PA12{slash}USART1_RTS{slash}CAN_TX{slash}USB_DP{slash}TIM1_ETR-Pad33)") (class "Default")
      (node (ref "IC101") (pin "33") (pinfunction "PA12/USART1_RTS/CAN_TX/USB_DP/TIM1_ETR_33") (pintype "bidirectional"))
    )
    (net (code "59") (name "unconnected-(IC101-PB0{slash}ADC12_IN8{slash}TIM3_CH3[TIM1_CH2N]-Pad18)") (class "Default")
      (node (ref "IC101") (pin "18") (pinfunction "PB0/ADC12_IN8/TIM3_CH3[TIM1_CH2N]_18") (pintype "bidirectional"))
    )
    (net (code "60") (name "unconnected-(IC101-PB1{slash}ADC12_IN9{slash}TIM3_CH4[TIM1_CH3N]-Pad19)") (class "Default")
      (node (ref "IC101") (pin "19") (pinfunction "PB1/ADC12_IN9/TIM3_CH4[TIM1_CH3N]_19") (pintype "bidirectional"))
    )
    (net (code "61") (name "unconnected-(IC101-PB2{slash}BOOT1-Pad20)") (class "Default")
      (node (ref "IC101") (pin "20") (pinfunction "PB2/BOOT1_20") (pintype "bidirectional"))
    )
    (net (code "62") (name "unconnected-(IC101-PB5{slash}I2C1_SMBAL[TIM3_CH2{slash}SPI1_MOSI]-Pad41)") (class "Default")
      (node (ref "IC101") (pin "41") (pinfunction "PB5/I2C1_SMBAL[TIM3_CH2/SPI1_MOSI]_41") (pintype "bidirectional"))
    )
    (net (code "63") (name "unconnected-(IC101-PB8{slash}TIM4_CH3[I2C1_SCL{slash}CAN_RX]-Pad45)") (class "Default")
      (node (ref "IC101") (pin "45") (pinfunction "PB8/TIM4_CH3[I2C1_SCL/CAN_RX]_45") (pintype "bidirectional"))
    )
    (net (code "64") (name "unconnected-(IC101-PB9{slash}TIM4_CH4[I2C1_SDA{slash}CAN_TX]-Pad46)") (class "Default")
      (node (ref "IC101") (pin "46") (pinfunction "PB9/TIM4_CH4[I2C1_SDA/CAN_TX]_46") (pintype "bidirectional"))
    )
    (net (code "65") (name "unconnected-(IC101-PB12{slash}SPI2_NSS{slash}I2C2_SMBAL{slash}USART3_CK{slash}TIM1_BKIN-Pad25)") (class "Default")
      (node (ref "IC101") (pin "25") (pinfunction "PB12/SPI2_NSS/I2C2_SMBAL/USART3_CK/TIM1_BKIN_25") (pintype "bidirectional"))
    )
    (net (code "66") (name "unconnected-(IC101-PB13{slash}SPI2_SCK{slash}USART3_CTS{slash}TIM1_CH1N-Pad26)") (class "Default")
      (node (ref "IC101") (pin "26") (pinfunction "PB13/SPI2_SCK/USART3_CTS/TIM1_CH1N_26") (pintype "bidirectional"))
    )
    (net (code "67") (name "unconnected-(IC101-PB14{slash}SPI2_MISO{slash}USART3_RTS{slash}TIM1_CH2N-Pad27)") (class "Default")
      (node (ref "IC101") (pin "27") (pinfunction "PB14/SPI2_MISO/USART3_RTS/TIM1_CH2N_27") (pintype "bidirectional"))
    )
    (net (code "68") (name "unconnected-(IC101-PB15{slash}SPI2_MOSI{slash}TIM1_CH3N-Pad28)") (class "Default")
      (node (ref "IC101") (pin "28") (pinfunction "PB15/SPI2_MOSI/TIM1_CH3N_28") (pintype "bidirectional"))
    )
    (net (code "69") (name "unconnected-(IC101-PC14{slash}OSC32_IN-Pad3)") (class "Default")
      (node (ref "IC101") (pin "3") (pinfunction "PC14/OSC32_IN_3") (pintype "bidirectional"))
    )
    (net (code "70") (name "unconnected-(IC101-PC15{slash}OSC32_OUT-Pad4)") (class "Default")
      (node (ref "IC101") (pin "4") (pinfunction "PC15/OSC32_OUT_4") (pintype "bidirectional"))
    )
    (net (code "71") (name "unconnected-(IC101-VBAT-Pad1)") (class "Default")
      (node (ref "IC101") (pin "1") (pinfunction "VBAT_1") (pintype "input"))
    )
    (net (code "72") (name "unconnected-(IC201-JNTRST[PB4{slash}TIM3_CH1{slash}SPI1_MISO]-Pad40)") (class "Default")
      (node (ref "IC201") (pin "40") (pinfunction "JNTRST[PB4/TIM3_CH1/SPI1_MISO]_40") (pintype "bidirectional"))
    )
    (net (code "73") (name "unconnected-(IC201-JTDI[PA15{slash}TIM2_CH1_ETR{slash}SPI1_NSS]-Pad38)") (class "Default")
      (node (ref "IC201") (pin "38") (pinfunction "JTDI[PA15/TIM2_CH1_ETR/SPI1_NSS]_38") (pintype "bidirectional"))
    )
    (net (code "74") (name "unconnected-(IC201-PA4{slash}SPI1_NSS{slash}USART2_CK{slash}ADC12_IN4-Pad14)") (class "Default")
      (node (ref "IC201") (pin "14") (pinfunction "PA4/SPI1_NSS/USART2_CK/ADC12_IN4_14") (pintype "bidirectional"))
    )
    (net (code "75") (name "unconnected-(IC201-PA5{slash}SPI1_SCK{slash}ADC12_IN5-Pad15)") (class "Default")
      (node (ref "IC201") (pin "15") (pinfunction "PA5/SPI1_SCK/ADC12_IN5_15") (pintype "bidirectional"))
    )
    (net (code "76") (name "unconnected-(IC201-PA6{slash}SPI1_MISO{slash}ADC12_IN6{slash}TIM3_CH1[TIM1_BKIN]-Pad16)") (class "Default")
      (node (ref "IC201") (pin "16") (pinfunction "PA6/SPI1_MISO/ADC12_IN6/TIM3_CH1[TIM1_BKIN]_16") (pintype "bidirectional"))
    )
    (net (code "77") (name "unconnected-(IC201-PA7{slash}SPI1_MOSI{slash}ADC12_IN7{slash}TIM3_CH2[TIM1_CH1N]-Pad17)") (class "Default")
      (node (ref "IC201") (pin "17") (pinfunction "PA7/SPI1_MOSI/ADC12_IN7/TIM3_CH2[TIM1_CH1N]_17") (pintype "bidirectional"))
    )
    (net (code "78") (name "unconnected-(IC201-PA8{slash}USART1_CK{slash}TIM1_CH1{slash}MCO-Pad29)") (class "Default")
      (node (ref "IC201") (pin "29") (pinfunction "PA8/USART1_CK/TIM1_CH1/MCO_29") (pintype "bidirectional"))
    )
    (net (code "79") (name "unconnected-(IC201-PA11{slash}USART1_CTS{slash}CAN_RX{slash}USB_DM{slash}TIM1_CH4-Pad32)") (class "Default")
      (node (ref "IC201") (pin "32") (pinfunction "PA11/USART1_CTS/CAN_RX/USB_DM/TIM1_CH4_32") (pintype "power_in"))
    )
    (net (code "80") (name "unconnected-(IC201-PA12{slash}USART1_RTS{slash}CAN_TX{slash}USB_DP{slash}TIM1_ETR-Pad33)") (class "Default")
      (node (ref "IC201") (pin "33") (pinfunction "PA12/USART1_RTS/CAN_TX/USB_DP/TIM1_ETR_33") (pintype "bidirectional"))
    )
    (net (code "81") (name "unconnected-(IC201-PB0{slash}ADC12_IN8{slash}TIM3_CH3[TIM1_CH2N]-Pad18)") (class "Default")
      (node (ref "IC201") (pin "18") (pinfunction "PB0/ADC12_IN8/TIM3_CH3[TIM1_CH2N]_18") (pintype "bidirectional"))
    )
    (net (code "82") (name "unconnected-(IC201-PB1{slash}ADC12_IN9{slash}TIM3_CH4[TIM1_CH3N]-Pad19)") (class "Default")
      (node (ref "IC201") (pin "19") (pinfunction "PB1/ADC12_IN9/TIM3_CH4[TIM1_CH3N]_19") (pintype "bidirectional"))
    )
    (net (code "83") (name "unconnected-(IC201-PB2{slash}BOOT1-Pad20)") (class "Default")
      (node (ref "IC201") (pin "20") (pinfunction "PB2/BOOT1_20") (pintype "bidirectional"))
    )
    (net (code "84") (name "unconnected-(IC201-PB5{slash}I2C1_SMBAL[TIM3_CH2{slash}SPI1_MOSI]-Pad41)") (class "Default")
      (node (ref "IC201") (pin "41") (pinfunction "PB5/I2C1_SMBAL[TIM3_CH2/SPI1_MOSI]_41") (pintype "bidirectional"))
    )
    (net (code "85") (name "unconnected-(IC201-PB8{slash}TIM4_CH3[I2C1_SCL{slash}CAN_RX]-Pad45)") (class "Default")
      (node (ref "IC201") (pin "45") (pinfunction "PB8/TIM4_CH3[I2C1_SCL/CAN_RX]_45") (pintype "bidirectional"))
    )
    (net (code "86") (name "unconnected-(IC201-PB9{slash}TIM4_CH4[I2C1_SDA{slash}CAN_TX]-Pad46)") (class "Default")
      (node (ref "IC201") (pin "46") (pinfunction "PB9/TIM4_CH4[I2C1_SDA/CAN_TX]_46") (pintype "bidirectional"))
    )
    (net (code "87") (name "unconnected-(IC201-PB12{slash}SPI2_NSS{slash}I2C2_SMBAL{slash}USART3_CK{slash}TIM1_BKIN-Pad25)") (class "Default")
      (node (ref "IC201") (pin "25") (pinfunction "PB12/SPI2_NSS/I2C2_SMBAL/USART3_CK/TIM1_BKIN_25") (pintype "bidirectional"))
    )
    (net (code "88") (name "unconnected-(IC201-PB13{slash}SPI2_SCK{slash}USART3_CTS{slash}TIM1_CH1N-Pad26)") (class "Default")
      (node (ref "IC201") (pin "26") (pinfunction "PB13/SPI2_SCK/USART3_CTS/TIM1_CH1N_26") (pintype "bidirectional"))
    )
    (net (code "89") (name "unconnected-(IC201-PB14{slash}SPI2_MISO{slash}USART3_RTS{slash}TIM1_CH2N-Pad27)") (class "Default")
      (node (ref "IC201") (pin "27") (pinfunction "PB14/SPI2_MISO/USART3_RTS/TIM1_CH2N_27") (pintype "bidirectional"))
    )
    (net (code "90") (name "unconnected-(IC201-PB15{slash}SPI2_MOSI{slash}TIM1_CH3N-Pad28)") (class "Default")
      (node (ref "IC201") (pin "28") (pinfunction "PB15/SPI2_MOSI/TIM1_CH3N_28") (pintype "bidirectional"))
    )
    (net (code "91") (name "unconnected-(IC201-PC14{slash}OSC32_IN-Pad3)") (class "Default")
      (node (ref "IC201") (pin "3") (pinfunction "PC14/OSC32_IN_3") (pintype "bidirectional"))
    )
    (net (code "92") (name "unconnected-(IC201-PC15{slash}OSC32_OUT-Pad4)") (class "Default")
      (node (ref "IC201") (pin "4") (pinfunction "PC15/OSC32_OUT_4") (pintype "bidirectional"))
    )
    (net (code "93") (name "unconnected-(IC201-VBAT-Pad1)") (class "Default")
      (node (ref "IC201") (pin "1") (pinfunction "VBAT_1") (pintype "input"))
    )
  )
)
